# ArduinoMicroShield1_0v.net
KiCad netlist of a schematic drawn in EAGLE
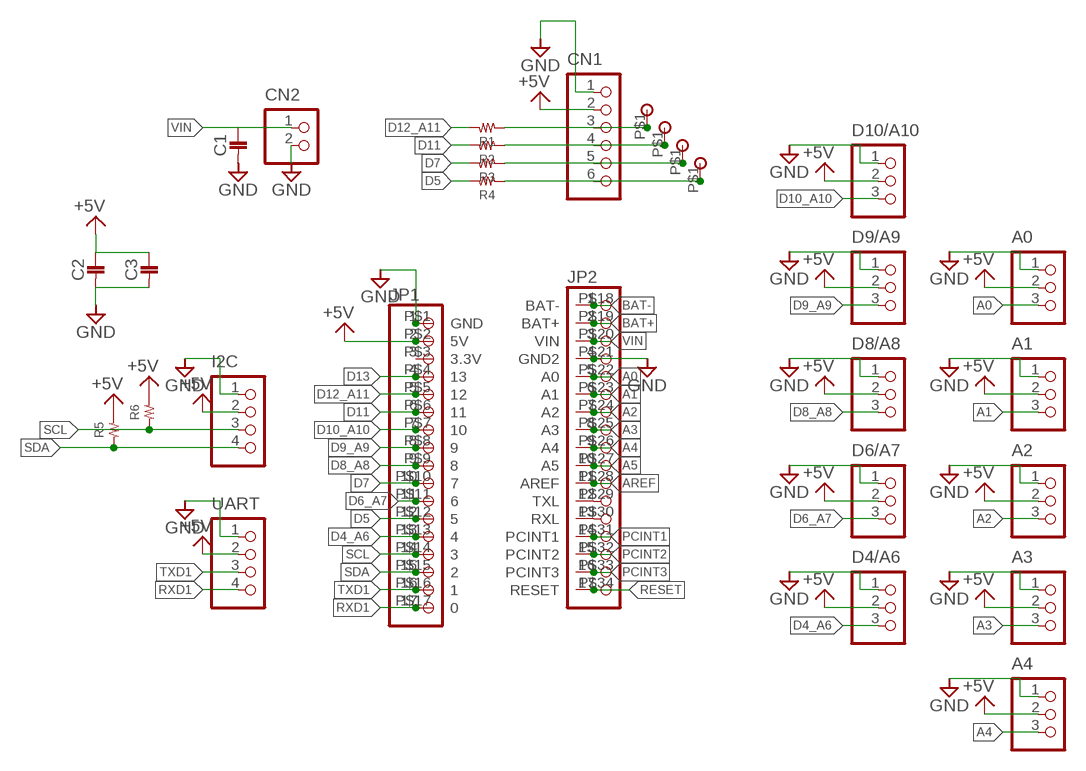
[diagram p0: schematic, sheet 1]

(export (version "E")
  (design (tool "Eeschema 10.0.6"))
  (components
    (comp (ref "A0")
      (value "B3B-PH-K-S")
      (footprint "eagle-import:B3B-PH-K-S")
      (libsource (lib "eagle-import") (part "B3B-PH-K-S"))
    )
    (comp (ref "A1")
      (value "B3B-PH-K-S")
      (footprint "eagle-import:B3B-PH-K-S")
      (libsource (lib "eagle-import") (part "B3B-PH-K-S"))
    )
    (comp (ref "A2")
      (value "B3B-PH-K-S")
      (footprint "eagle-import:B3B-PH-K-S")
      (libsource (lib "eagle-import") (part "B3B-PH-K-S"))
    )
    (comp (ref "A3")
      (value "B3B-PH-K-S")
      (footprint "eagle-import:B3B-PH-K-S")
      (libsource (lib "eagle-import") (part "B3B-PH-K-S"))
    )
    (comp (ref "A4")
      (value "B3B-PH-K-S")
      (footprint "eagle-import:B3B-PH-K-S")
      (libsource (lib "eagle-import") (part "B3B-PH-K-S"))
    )
    (comp (ref "C1")
      (value "1608")
      (footprint "eagle-import:1608")
      (libsource (lib "eagle-import") (part "1608"))
    )
    (comp (ref "C2")
      (value "1608")
      (footprint "eagle-import:1608")
      (libsource (lib "eagle-import") (part "1608"))
    )
    (comp (ref "C3")
      (value "1608")
      (footprint "eagle-import:1608")
      (libsource (lib "eagle-import") (part "1608"))
    )
    (comp (ref "CN1")
      (value "B6B-PH-K-S")
      (footprint "eagle-import:B6B-PH-K-S")
      (libsource (lib "eagle-import") (part "B6B-PH-K-S"))
    )
    (comp (ref "CN2")
      (value "S2B-PH-K-S")
      (footprint "eagle-import:S2B-PH-K-S")
      (libsource (lib "eagle-import") (part "S2B-PH-K-S"))
    )
    (comp (ref "D4/A6")
      (value "B3B-PH-K-S")
      (footprint "eagle-import:B3B-PH-K-S")
      (libsource (lib "eagle-import") (part "B3B-PH-K-S"))
    )
    (comp (ref "D6/A7")
      (value "B3B-PH-K-S")
      (footprint "eagle-import:B3B-PH-K-S")
      (libsource (lib "eagle-import") (part "B3B-PH-K-S"))
    )
    (comp (ref "D8/A8")
      (value "B3B-PH-K-S")
      (footprint "eagle-import:B3B-PH-K-S")
      (libsource (lib "eagle-import") (part "B3B-PH-K-S"))
    )
    (comp (ref "D9/A9")
      (value "B3B-PH-K-S")
      (footprint "eagle-import:B3B-PH-K-S")
      (libsource (lib "eagle-import") (part "B3B-PH-K-S"))
    )
    (comp (ref "D10/A10")
      (value "B3B-PH-K-S")
      (footprint "eagle-import:B3B-PH-K-S")
      (libsource (lib "eagle-import") (part "B3B-PH-K-S"))
    )
    (comp (ref "I2C")
      (value "B4B-PH-K-S")
      (footprint "eagle-import:B4B-PH-K-S")
      (libsource (lib "eagle-import") (part "B4B-PH-K-S"))
    )
    (comp (ref "JP1")
      (value "PINHD-1X17")
      (footprint "eagle-import:1X17")
      (libsource (lib "eagle-import") (part "PINHD-1X17"))
    )
    (comp (ref "JP2")
      (value "PINHD-1X17")
      (footprint "eagle-import:1X17")
      (libsource (lib "eagle-import") (part "PINHD-1X17"))
    )
    (comp (ref "R1")
      (value "RESISTOR__SMD")
      (footprint "eagle-import:1608")
      (libsource (lib "eagle-import") (part "RESISTOR__SMD"))
    )
    (comp (ref "R2")
      (value "RESISTOR__SMD")
      (footprint "eagle-import:1608")
      (libsource (lib "eagle-import") (part "RESISTOR__SMD"))
    )
    (comp (ref "R3")
      (value "RESISTOR__SMD")
      (footprint "eagle-import:1608")
      (libsource (lib "eagle-import") (part "RESISTOR__SMD"))
    )
    (comp (ref "R4")
      (value "RESISTOR__SMD")
      (footprint "eagle-import:1608")
      (libsource (lib "eagle-import") (part "RESISTOR__SMD"))
    )
    (comp (ref "R5")
      (value "RESISTOR__SMD")
      (footprint "eagle-import:1608")
      (libsource (lib "eagle-import") (part "RESISTOR__SMD"))
    )
    (comp (ref "R6")
      (value "RESISTOR__SMD")
      (footprint "eagle-import:1608")
      (libsource (lib "eagle-import") (part "RESISTOR__SMD"))
    )
    (comp (ref "U$1")
      (value "ARDUINO_ASTAR_MICRO")
      (footprint "eagle-import:ARDUINO_ASTAR_MICRO")
      (libsource (lib "eagle-import") (part "ARDUINO_ASTAR_MICRO"))
    )
    (comp (ref "U$31")
      (value "CHECK_0.8MM")
      (footprint "eagle-import:CHECK_0.8MM")
      (libsource (lib "eagle-import") (part "CHECK_0.8MM"))
    )
    (comp (ref "U$32")
      (value "CHECK_0.8MM")
      (footprint "eagle-import:CHECK_0.8MM")
      (libsource (lib "eagle-import") (part "CHECK_0.8MM"))
    )
    (comp (ref "U$36")
      (value "CHECK_0.8MM")
      (footprint "eagle-import:CHECK_0.8MM")
      (libsource (lib "eagle-import") (part "CHECK_0.8MM"))
    )
    (comp (ref "U$37")
      (value "CHECK_0.8MM")
      (footprint "eagle-import:CHECK_0.8MM")
      (libsource (lib "eagle-import") (part "CHECK_0.8MM"))
    )
    (comp (ref "UART")
      (value "B4B-PH-K-S")
      (footprint "eagle-import:B4B-PH-K-S")
      (libsource (lib "eagle-import") (part "B4B-PH-K-S"))
    )
  )
  (nets
    (net (code "1") (name "+5V") (class "Default")
      (node (ref "A0") (pin "2") (pinfunction "2_2") (pintype "passive"))
      (node (ref "A1") (pin "2") (pinfunction "2_2") (pintype "passive"))
      (node (ref "A2") (pin "2") (pinfunction "2_2") (pintype "passive"))
      (node (ref "A3") (pin "2") (pinfunction "2_2") (pintype "passive"))
      (node (ref "A4") (pin "2") (pinfunction "2_2") (pintype "passive"))
      (node (ref "C2") (pin "P$1") (pinfunction "1_P$1") (pintype "passive"))
      (node (ref "C3") (pin "P$1") (pinfunction "1_P$1") (pintype "passive"))
      (node (ref "CN1") (pin "2") (pinfunction "2_2") (pintype "passive"))
      (node (ref "D10/A10") (pin "2") (pinfunction "2_2") (pintype "passive"))
      (node (ref "D4/A6") (pin "2") (pinfunction "2_2") (pintype "passive"))
      (node (ref "D6/A7") (pin "2") (pinfunction "2_2") (pintype "passive"))
      (node (ref "D8/A8") (pin "2") (pinfunction "2_2") (pintype "passive"))
      (node (ref "D9/A9") (pin "2") (pinfunction "2_2") (pintype "passive"))
      (node (ref "I2C") (pin "2") (pinfunction "2_2") (pintype "passive"))
      (node (ref "JP1") (pin "2") (pinfunction "2_2") (pintype "passive"))
      (node (ref "R5") (pin "2") (pinfunction "P$2_2") (pintype "passive"))
      (node (ref "R6") (pin "2") (pinfunction "P$2_2") (pintype "passive"))
      (node (ref "U$1") (pin "P$2") (pinfunction "5V_P$2") (pintype "bidirectional"))
      (node (ref "UART") (pin "2") (pinfunction "2_2") (pintype "passive"))
    )
    (net (code "2") (name "A0") (class "Default")
      (node (ref "A0") (pin "3") (pinfunction "3_3") (pintype "passive"))
      (node (ref "JP2") (pin "5") (pinfunction "5_5") (pintype "passive"))
      (node (ref "U$1") (pin "P$22") (pinfunction "A0_P$22") (pintype "bidirectional"))
    )
    (net (code "3") (name "A1") (class "Default")
      (node (ref "A1") (pin "3") (pinfunction "3_3") (pintype "passive"))
      (node (ref "JP2") (pin "6") (pinfunction "6_6") (pintype "passive"))
      (node (ref "U$1") (pin "P$23") (pinfunction "A1_P$23") (pintype "bidirectional"))
    )
    (net (code "4") (name "A2") (class "Default")
      (node (ref "A2") (pin "3") (pinfunction "3_3") (pintype "passive"))
      (node (ref "JP2") (pin "7") (pinfunction "7_7") (pintype "passive"))
      (node (ref "U$1") (pin "P$24") (pinfunction "A2_P$24") (pintype "bidirectional"))
    )
    (net (code "5") (name "A3") (class "Default")
      (node (ref "A3") (pin "3") (pinfunction "3_3") (pintype "passive"))
      (node (ref "JP2") (pin "8") (pinfunction "8_8") (pintype "passive"))
      (node (ref "U$1") (pin "P$25") (pinfunction "A3_P$25") (pintype "bidirectional"))
    )
    (net (code "6") (name "A4") (class "Default")
      (node (ref "A4") (pin "3") (pinfunction "3_3") (pintype "passive"))
      (node (ref "JP2") (pin "9") (pinfunction "9_9") (pintype "passive"))
      (node (ref "U$1") (pin "P$26") (pinfunction "A4_P$26") (pintype "bidirectional"))
    )
    (net (code "7") (name "A5") (class "Default")
      (node (ref "JP2") (pin "10") (pinfunction "10_10") (pintype "passive"))
      (node (ref "U$1") (pin "P$27") (pinfunction "A5_P$27") (pintype "bidirectional"))
    )
    (net (code "8") (name "AREF") (class "Default")
      (node (ref "JP2") (pin "11") (pinfunction "11_11") (pintype "passive"))
      (node (ref "U$1") (pin "P$28") (pinfunction "AREF_P$28") (pintype "bidirectional"))
    )
    (net (code "9") (name "BAT+") (class "Default")
      (node (ref "JP2") (pin "2") (pinfunction "2_2") (pintype "passive"))
      (node (ref "U$1") (pin "P$19") (pinfunction "BAT+_P$19") (pintype "bidirectional"))
    )
    (net (code "10") (name "BAT-") (class "Default")
      (node (ref "JP2") (pin "1") (pinfunction "1_1") (pintype "passive"))
      (node (ref "U$1") (pin "P$18") (pinfunction "BAT-_P$18") (pintype "bidirectional"))
    )
    (net (code "11") (name "D4_A6") (class "Default")
      (node (ref "D4/A6") (pin "3") (pinfunction "3_3") (pintype "passive"))
      (node (ref "JP1") (pin "13") (pinfunction "13_13") (pintype "passive"))
      (node (ref "U$1") (pin "P$13") (pinfunction "4_P$13") (pintype "bidirectional"))
    )
    (net (code "12") (name "D5") (class "Default")
      (node (ref "JP1") (pin "12") (pinfunction "12_12") (pintype "passive"))
      (node (ref "R4") (pin "2") (pinfunction "P$2_2") (pintype "passive"))
      (node (ref "U$1") (pin "P$12") (pinfunction "5_P$12") (pintype "bidirectional"))
    )
    (net (code "13") (name "D6_A7") (class "Default")
      (node (ref "D6/A7") (pin "3") (pinfunction "3_3") (pintype "passive"))
      (node (ref "JP1") (pin "11") (pinfunction "11_11") (pintype "passive"))
      (node (ref "U$1") (pin "P$11") (pinfunction "6_P$11") (pintype "bidirectional"))
    )
    (net (code "14") (name "D7") (class "Default")
      (node (ref "JP1") (pin "10") (pinfunction "10_10") (pintype "passive"))
      (node (ref "R3") (pin "2") (pinfunction "P$2_2") (pintype "passive"))
      (node (ref "U$1") (pin "P$10") (pinfunction "7_P$10") (pintype "bidirectional"))
    )
    (net (code "15") (name "D8_A8") (class "Default")
      (node (ref "D8/A8") (pin "3") (pinfunction "3_3") (pintype "passive"))
      (node (ref "JP1") (pin "9") (pinfunction "9_9") (pintype "passive"))
      (node (ref "U$1") (pin "P$9") (pinfunction "8_P$9") (pintype "bidirectional"))
    )
    (net (code "16") (name "D9_A9") (class "Default")
      (node (ref "D9/A9") (pin "3") (pinfunction "3_3") (pintype "passive"))
      (node (ref "JP1") (pin "8") (pinfunction "8_8") (pintype "passive"))
      (node (ref "U$1") (pin "P$8") (pinfunction "9_P$8") (pintype "bidirectional"))
    )
    (net (code "17") (name "D10_A10") (class "Default")
      (node (ref "D10/A10") (pin "3") (pinfunction "3_3") (pintype "passive"))
      (node (ref "JP1") (pin "7") (pinfunction "7_7") (pintype "passive"))
      (node (ref "U$1") (pin "P$7") (pinfunction "10_P$7") (pintype "bidirectional"))
    )
    (net (code "18") (name "D11") (class "Default")
      (node (ref "JP1") (pin "6") (pinfunction "6_6") (pintype "passive"))
      (node (ref "R2") (pin "2") (pinfunction "P$2_2") (pintype "passive"))
      (node (ref "U$1") (pin "P$6") (pinfunction "11_P$6") (pintype "bidirectional"))
    )
    (net (code "19") (name "D12_A11") (class "Default")
      (node (ref "JP1") (pin "5") (pinfunction "5_5") (pintype "passive"))
      (node (ref "R1") (pin "2") (pinfunction "P$2_2") (pintype "passive"))
      (node (ref "U$1") (pin "P$5") (pinfunction "12_P$5") (pintype "bidirectional"))
    )
    (net (code "20") (name "D13") (class "Default")
      (node (ref "JP1") (pin "4") (pinfunction "4_4") (pintype "passive"))
      (node (ref "U$1") (pin "P$4") (pinfunction "13_P$4") (pintype "bidirectional"))
    )
    (net (code "21") (name "GND") (class "Default")
      (node (ref "A0") (pin "1") (pinfunction "1_1") (pintype "passive"))
      (node (ref "A1") (pin "1") (pinfunction "1_1") (pintype "passive"))
      (node (ref "A2") (pin "1") (pinfunction "1_1") (pintype "passive"))
      (node (ref "A3") (pin "1") (pinfunction "1_1") (pintype "passive"))
      (node (ref "A4") (pin "1") (pinfunction "1_1") (pintype "passive"))
      (node (ref "C1") (pin "P$2") (pinfunction "2_P$2") (pintype "passive"))
      (node (ref "C2") (pin "P$2") (pinfunction "2_P$2") (pintype "passive"))
      (node (ref "C3") (pin "P$2") (pinfunction "2_P$2") (pintype "passive"))
      (node (ref "CN1") (pin "1") (pinfunction "1_1") (pintype "passive"))
      (node (ref "CN2") (pin "2") (pinfunction "2_2") (pintype "passive"))
      (node (ref "D10/A10") (pin "1") (pinfunction "1_1") (pintype "passive"))
      (node (ref "D4/A6") (pin "1") (pinfunction "1_1") (pintype "passive"))
      (node (ref "D6/A7") (pin "1") (pinfunction "1_1") (pintype "passive"))
      (node (ref "D8/A8") (pin "1") (pinfunction "1_1") (pintype "passive"))
      (node (ref "D9/A9") (pin "1") (pinfunction "1_1") (pintype "passive"))
      (node (ref "I2C") (pin "1") (pinfunction "1_1") (pintype "passive"))
      (node (ref "JP1") (pin "1") (pinfunction "1_1") (pintype "passive"))
      (node (ref "JP2") (pin "4") (pinfunction "4_4") (pintype "passive"))
      (node (ref "U$1") (pin "P$1") (pinfunction "GND_P$1") (pintype "bidirectional"))
      (node (ref "U$1") (pin "P$21") (pinfunction "GND2_P$21") (pintype "bidirectional"))
      (node (ref "UART") (pin "1") (pinfunction "1_1") (pintype "passive"))
    )
    (net (code "22") (name "Net-(R1-P$1)") (class "Default")
      (node (ref "CN1") (pin "3") (pinfunction "3_3") (pintype "passive"))
      (node (ref "R1") (pin "1") (pinfunction "P$1_1") (pintype "passive"))
      (node (ref "U$31") (pin "P$1") (pinfunction "P$1_P$1") (pintype "bidirectional"))
    )
    (net (code "23") (name "Net-(R2-P$1)") (class "Default")
      (node (ref "CN1") (pin "4") (pinfunction "4_4") (pintype "passive"))
      (node (ref "R2") (pin "1") (pinfunction "P$1_1") (pintype "passive"))
      (node (ref "U$32") (pin "P$1") (pinfunction "P$1_P$1") (pintype "bidirectional"))
    )
    (net (code "24") (name "Net-(R3-P$1)") (class "Default")
      (node (ref "CN1") (pin "5") (pinfunction "5_5") (pintype "passive"))
      (node (ref "R3") (pin "1") (pinfunction "P$1_1") (pintype "passive"))
      (node (ref "U$36") (pin "P$1") (pinfunction "P$1_P$1") (pintype "bidirectional"))
    )
    (net (code "25") (name "Net-(R4-P$1)") (class "Default")
      (node (ref "CN1") (pin "6") (pinfunction "6_6") (pintype "passive"))
      (node (ref "R4") (pin "1") (pinfunction "P$1_1") (pintype "passive"))
      (node (ref "U$37") (pin "P$1") (pinfunction "P$1_P$1") (pintype "bidirectional"))
    )
    (net (code "26") (name "Net-(U$1-3.3V)") (class "Default")
      (node (ref "JP1") (pin "3") (pinfunction "3_3") (pintype "passive"))
      (node (ref "U$1") (pin "P$3") (pinfunction "3.3V_P$3") (pintype "bidirectional"))
    )
    (net (code "27") (name "Net-(U$1-RXL)") (class "Default")
      (node (ref "JP2") (pin "13") (pinfunction "13_13") (pintype "passive"))
      (node (ref "U$1") (pin "P$30") (pinfunction "RXL_P$30") (pintype "bidirectional"))
    )
    (net (code "28") (name "Net-(U$1-TXL)") (class "Default")
      (node (ref "JP2") (pin "12") (pinfunction "12_12") (pintype "passive"))
      (node (ref "U$1") (pin "P$29") (pinfunction "TXL_P$29") (pintype "bidirectional"))
    )
    (net (code "29") (name "PCINT1") (class "Default")
      (node (ref "JP2") (pin "14") (pinfunction "14_14") (pintype "passive"))
      (node (ref "U$1") (pin "P$31") (pinfunction "PCINT1_P$31") (pintype "bidirectional"))
    )
    (net (code "30") (name "PCINT2") (class "Default")
      (node (ref "JP2") (pin "15") (pinfunction "15_15") (pintype "passive"))
      (node (ref "U$1") (pin "P$32") (pinfunction "PCINT2_P$32") (pintype "bidirectional"))
    )
    (net (code "31") (name "PCINT3") (class "Default")
      (node (ref "JP2") (pin "16") (pinfunction "16_16") (pintype "passive"))
      (node (ref "U$1") (pin "P$33") (pinfunction "PCINT3_P$33") (pintype "bidirectional"))
    )
    (net (code "32") (name "RESET") (class "Default")
      (node (ref "JP2") (pin "17") (pinfunction "17_17") (pintype "passive"))
      (node (ref "U$1") (pin "P$34") (pinfunction "RESET_P$34") (pintype "bidirectional"))
    )
    (net (code "33") (name "RXD1") (class "Default")
      (node (ref "JP1") (pin "17") (pinfunction "17_17") (pintype "passive"))
      (node (ref "U$1") (pin "P$17") (pinfunction "0_P$17") (pintype "bidirectional"))
      (node (ref "UART") (pin "4") (pinfunction "4_4") (pintype "passive"))
    )
    (net (code "34") (name "SCL") (class "Default")
      (node (ref "I2C") (pin "3") (pinfunction "3_3") (pintype "passive"))
      (node (ref "JP1") (pin "14") (pinfunction "14_14") (pintype "passive"))
      (node (ref "R6") (pin "1") (pinfunction "P$1_1") (pintype "passive"))
      (node (ref "U$1") (pin "P$14") (pinfunction "3_P$14") (pintype "bidirectional"))
    )
    (net (code "35") (name "SDA") (class "Default")
      (node (ref "I2C") (pin "4") (pinfunction "4_4") (pintype "passive"))
      (node (ref "JP1") (pin "15") (pinfunction "15_15") (pintype "passive"))
      (node (ref "R5") (pin "1") (pinfunction "P$1_1") (pintype "passive"))
      (node (ref "U$1") (pin "P$15") (pinfunction "2_P$15") (pintype "bidirectional"))
    )
    (net (code "36") (name "TXD1") (class "Default")
      (node (ref "JP1") (pin "16") (pinfunction "16_16") (pintype "passive"))
      (node (ref "U$1") (pin "P$16") (pinfunction "1_P$16") (pintype "bidirectional"))
      (node (ref "UART") (pin "3") (pinfunction "3_3") (pintype "passive"))
    )
    (net (code "37") (name "VIN") (class "Default")
      (node (ref "C1") (pin "P$1") (pinfunction "1_P$1") (pintype "passive"))
      (node (ref "CN2") (pin "1") (pinfunction "1_1") (pintype "passive"))
      (node (ref "JP2") (pin "3") (pinfunction "3_3") (pintype "passive"))
      (node (ref "U$1") (pin "P$20") (pinfunction "VIN_P$20") (pintype "bidirectional"))
    )
  )
)
